# Thermostat_Schematic.net
KiCad netlist of a schematic drawn in EAGLE
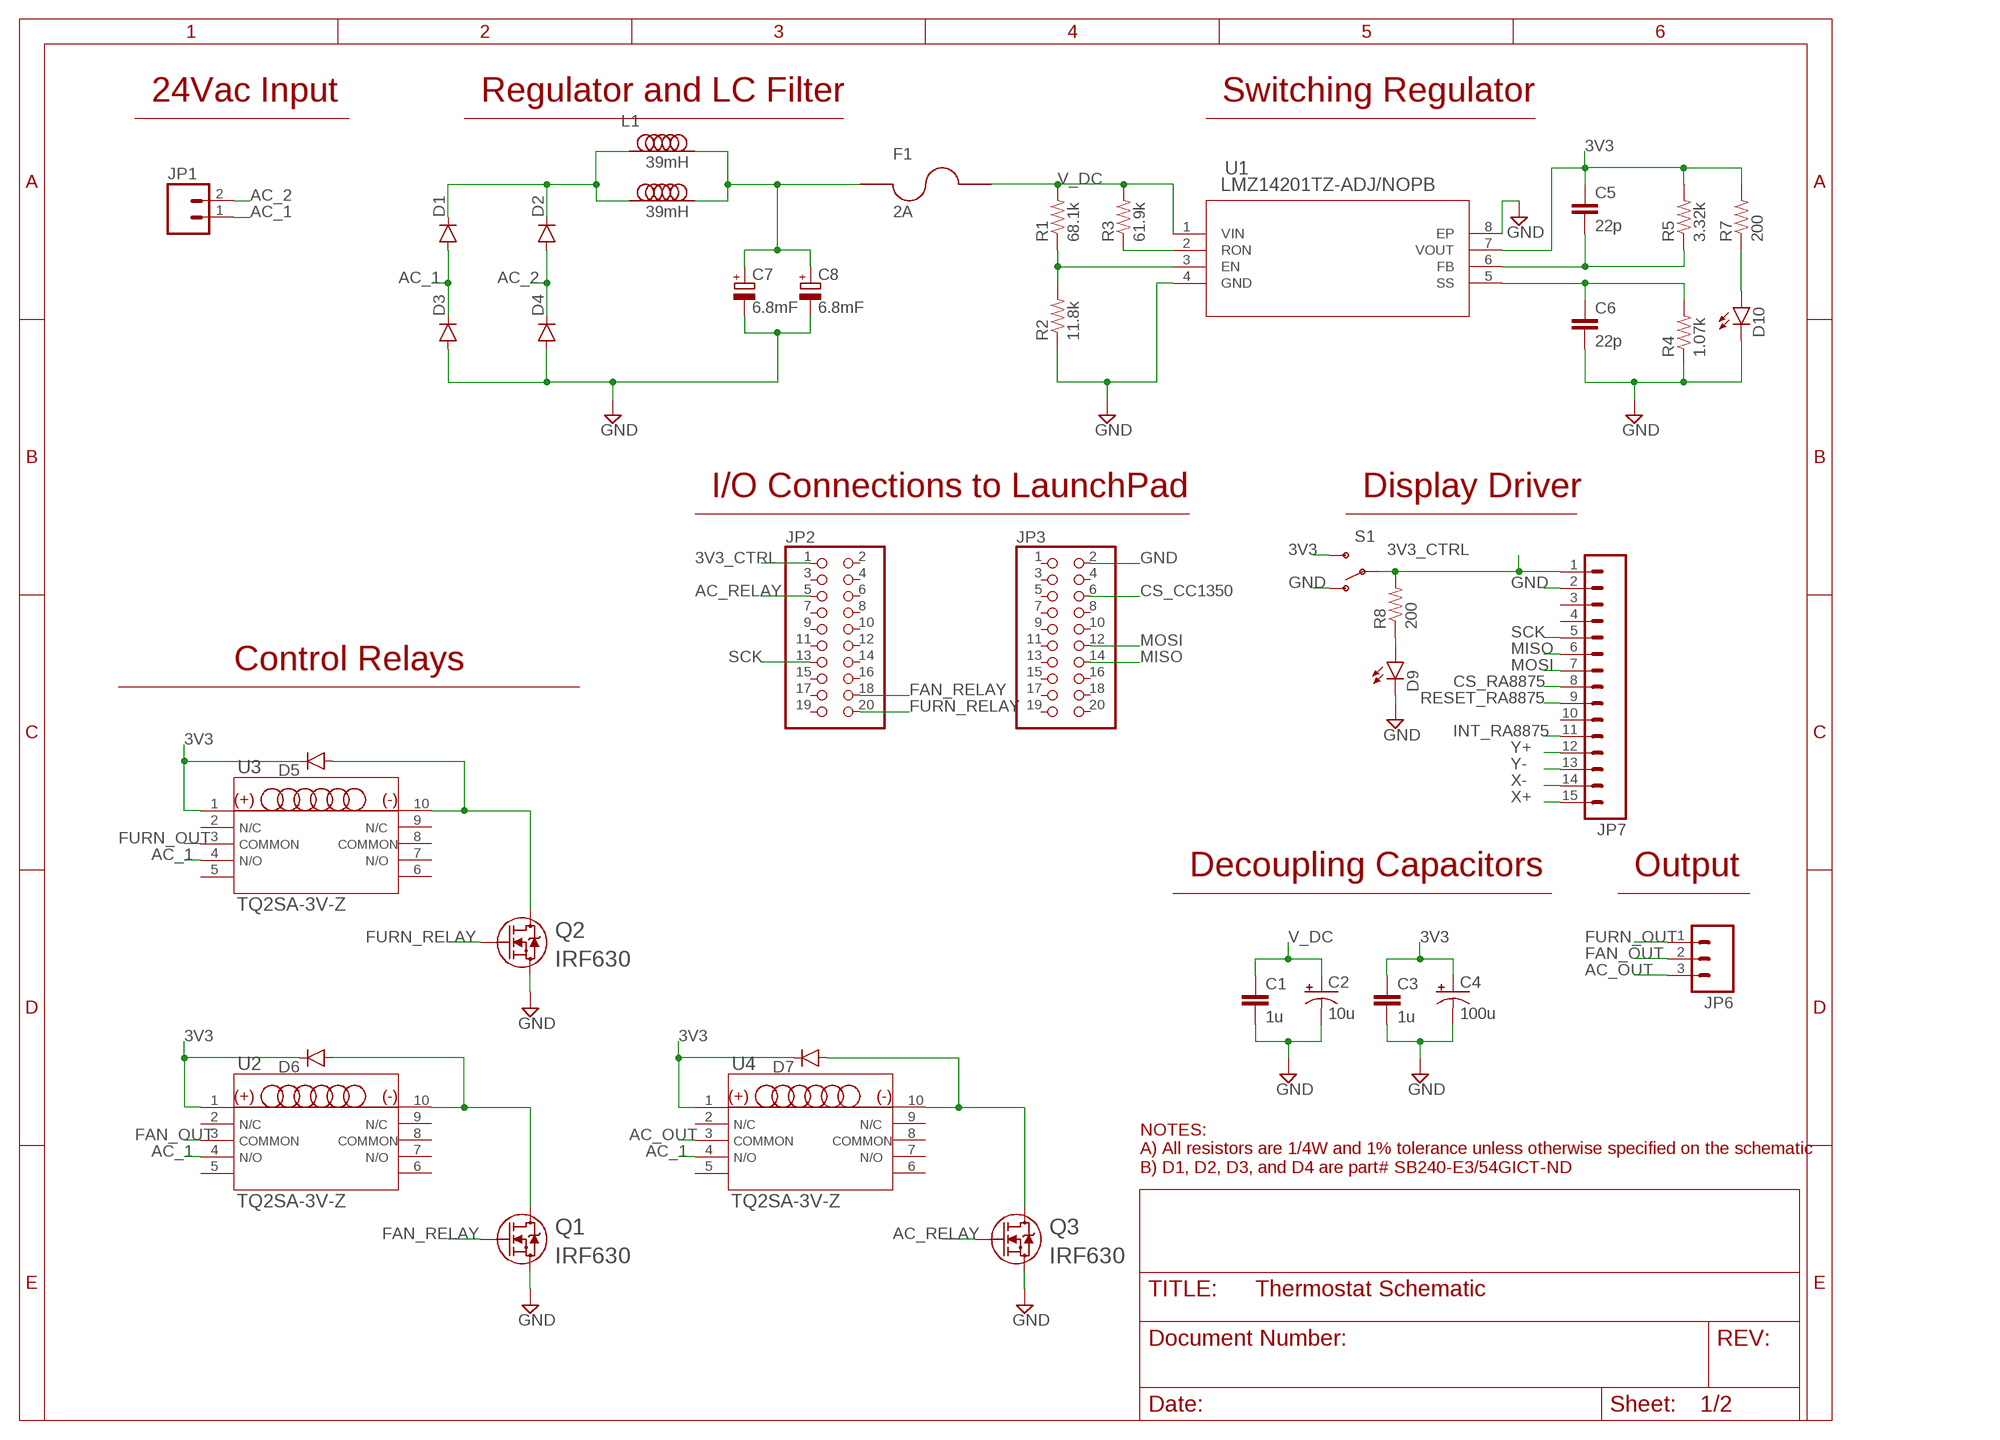
[diagram p0: schematic, sheet 1]
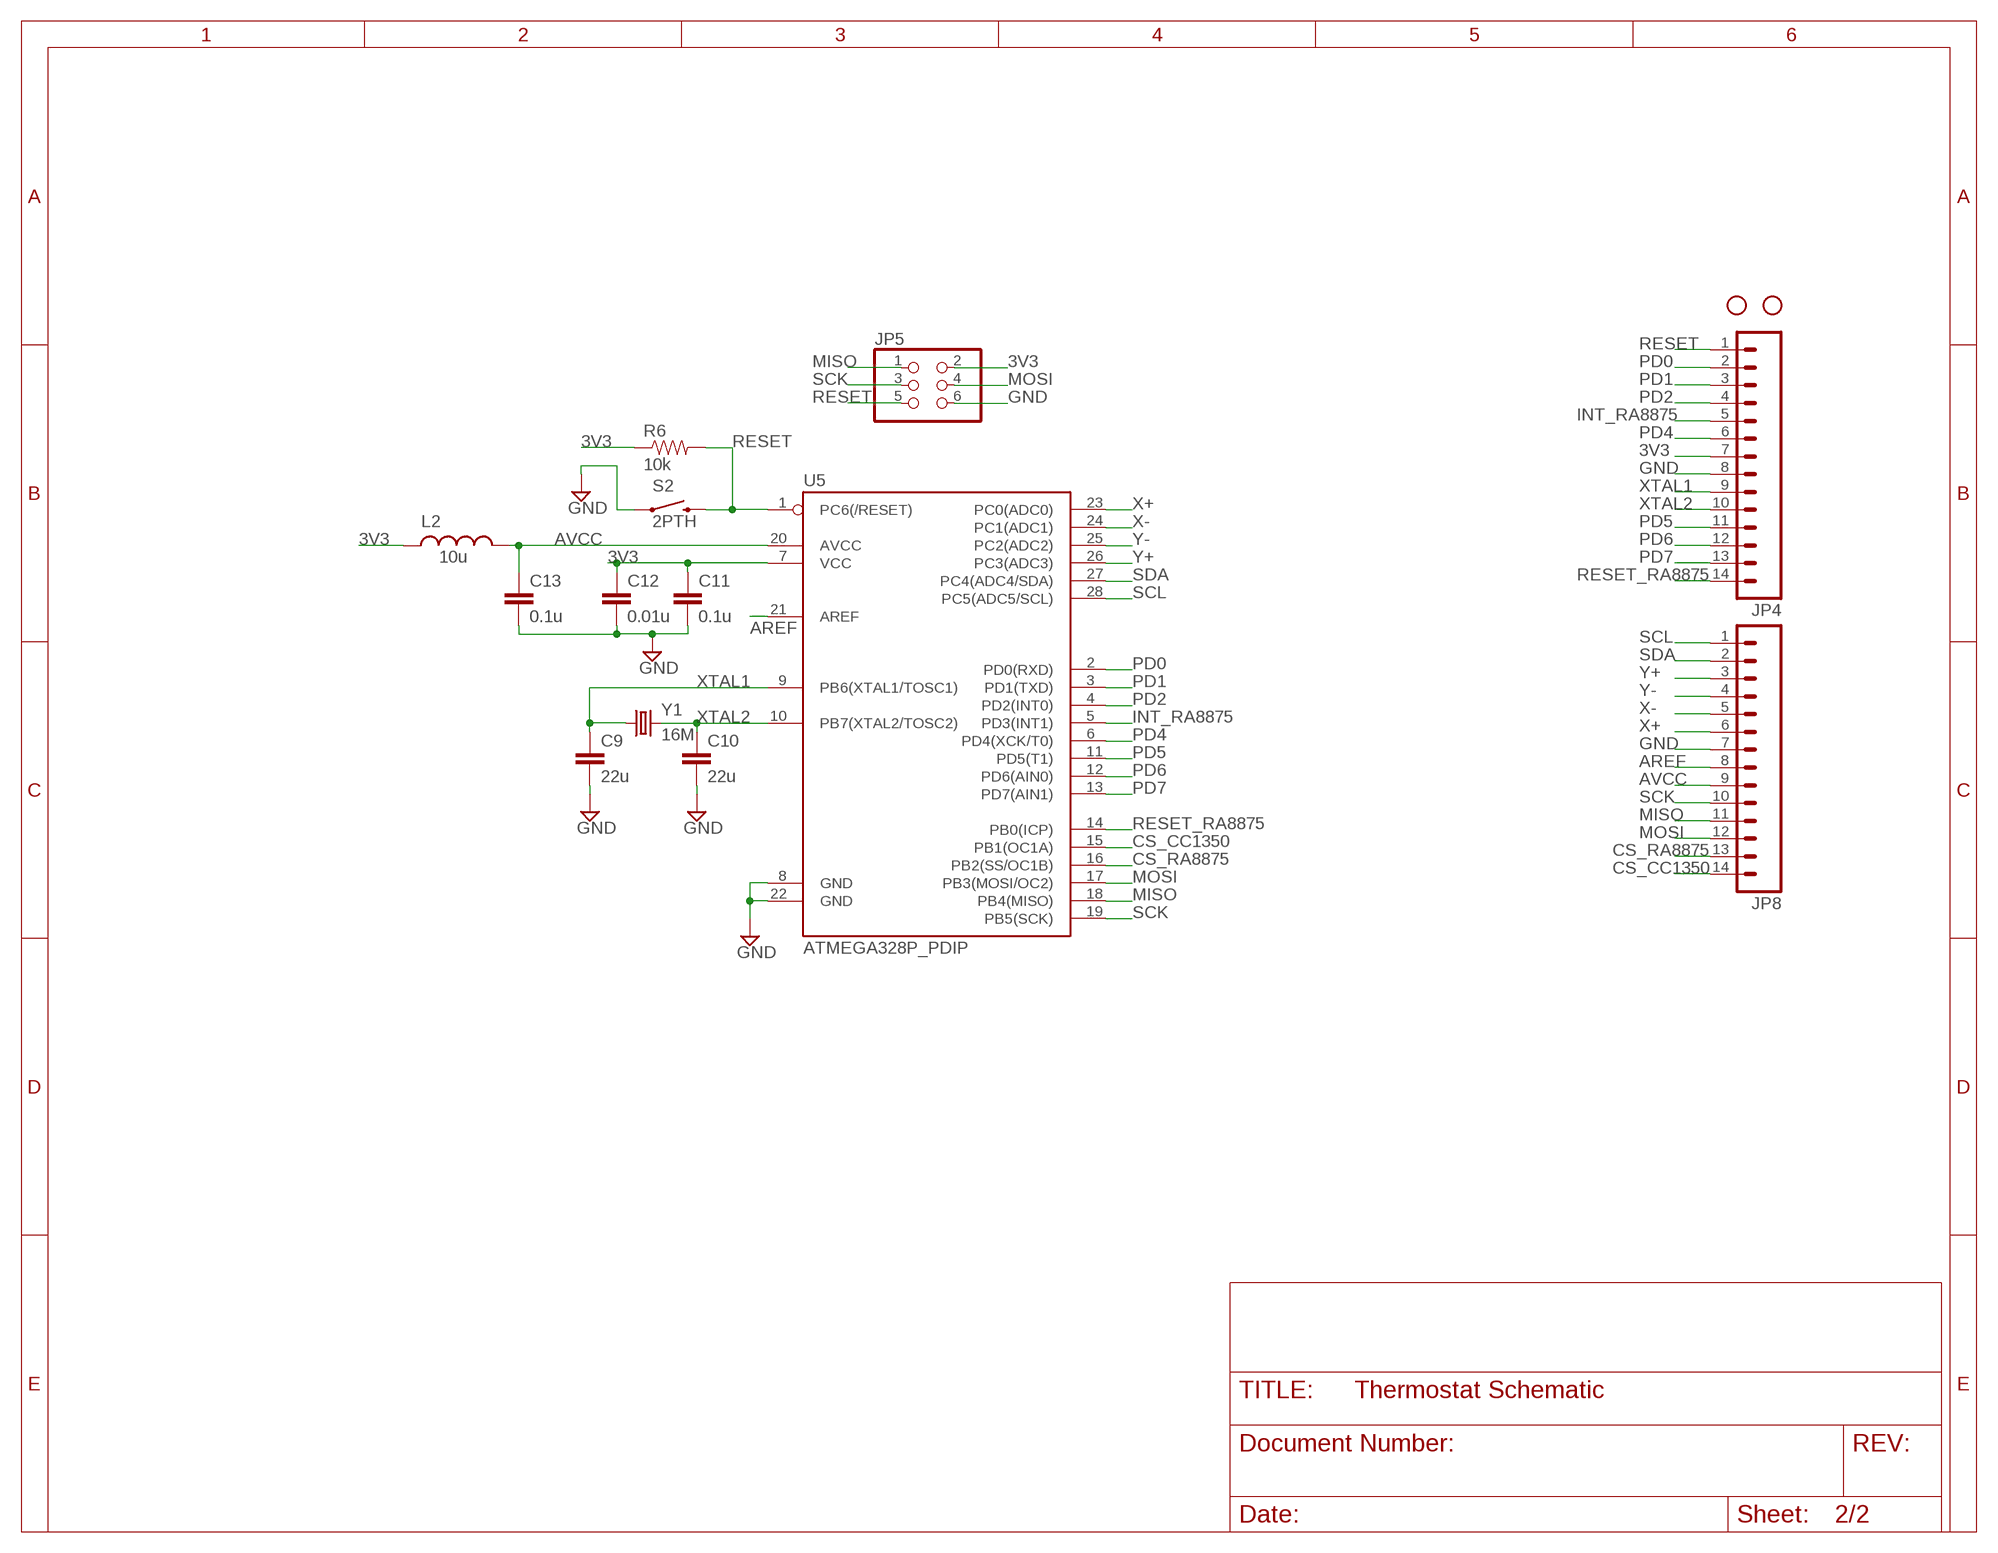
[diagram p1: schematic, sheet 2]

(export (version "E")
  (design (tool "Eeschema 10.0.6"))
  (components
    (comp (ref "C1")
      (value "1u")
      (footprint "eagle-import:CAP-PTH-5MM")
      (libsource (lib "eagle-import") (part "CAPPTH1"))
    )
    (comp (ref "C2")
      (value "10u")
      (footprint "eagle-import:CPOL-RADIAL-10UF-25V")
      (libsource (lib "eagle-import") (part "CAP_POLPTH2"))
    )
    (comp (ref "C3")
      (value "1u")
      (footprint "eagle-import:CAP-PTH-5MM")
      (libsource (lib "eagle-import") (part "CAPPTH1"))
    )
    (comp (ref "C4")
      (value "100u")
      (footprint "eagle-import:CPOL-RADIAL-1000UF-25V")
      (libsource (lib "eagle-import") (part "CAP_POLPTH4"))
    )
    (comp (ref "C5")
      (value "22p")
      (footprint "eagle-import:CAP-PTH-5MM")
      (libsource (lib "eagle-import") (part "CAPPTH1"))
    )
    (comp (ref "C6")
      (value "22p")
      (footprint "eagle-import:CAP-PTH-5MM")
      (libsource (lib "eagle-import") (part "CAPPTH1"))
    )
    (comp (ref "C7")
      (value "6.8mF")
      (footprint "eagle-import:E7,5-16")
      (libsource (lib "eagle-import") (part "CPOL-EUE7.5-16"))
    )
    (comp (ref "C8")
      (value "6.8mF")
      (footprint "eagle-import:E7,5-16")
      (libsource (lib "eagle-import") (part "CPOL-EUE7.5-16"))
    )
    (comp (ref "D1")
      (value "DIODEPTH")
      (footprint "eagle-import:DIODE-1N4001")
      (libsource (lib "eagle-import") (part "DIODEPTH"))
    )
    (comp (ref "D2")
      (value "DIODEPTH")
      (footprint "eagle-import:DIODE-1N4001")
      (libsource (lib "eagle-import") (part "DIODEPTH"))
    )
    (comp (ref "D3")
      (value "DIODEPTH")
      (footprint "eagle-import:DIODE-1N4001")
      (libsource (lib "eagle-import") (part "DIODEPTH"))
    )
    (comp (ref "D4")
      (value "DIODEPTH")
      (footprint "eagle-import:DIODE-1N4001")
      (libsource (lib "eagle-import") (part "DIODEPTH"))
    )
    (comp (ref "D5")
      (value "DIODEPTH")
      (footprint "eagle-import:DIODE-1N4001")
      (libsource (lib "eagle-import") (part "DIODEPTH"))
    )
    (comp (ref "D6")
      (value "DIODEPTH")
      (footprint "eagle-import:DIODE-1N4001")
      (libsource (lib "eagle-import") (part "DIODEPTH"))
    )
    (comp (ref "D7")
      (value "DIODEPTH")
      (footprint "eagle-import:DIODE-1N4001")
      (libsource (lib "eagle-import") (part "DIODEPTH"))
    )
    (comp (ref "D9")
      (value "LED1206")
      (footprint "eagle-import:LED-1206")
      (libsource (lib "eagle-import") (part "LED1206"))
    )
    (comp (ref "D10")
      (value "LED1206")
      (footprint "eagle-import:LED-1206")
      (libsource (lib "eagle-import") (part "LED1206"))
    )
    (comp (ref "F1")
      (value "2A")
      (footprint "eagle-import:36-3550-2-ND")
      (libsource (lib "eagle-import") (part "FUSEHOLDER_36-3550-2-ND"))
    )
    (comp (ref "JP1")
      (value "M023.5MM")
      (footprint "eagle-import:SCREWTERMINAL-3.5MM-2")
      (libsource (lib "eagle-import") (part "M023.5MM"))
    )
    (comp (ref "JP2")
      (value "PINHD-2X10")
      (footprint "eagle-import:2X10")
      (libsource (lib "eagle-import") (part "PINHD-2X10"))
    )
    (comp (ref "JP3")
      (value "PINHD-2X10")
      (footprint "eagle-import:2X10")
      (libsource (lib "eagle-import") (part "PINHD-2X10"))
    )
    (comp (ref "JP6")
      (value "M03SCREW")
      (footprint "eagle-import:SCREWTERMINAL-3.5MM-3")
      (libsource (lib "eagle-import") (part "M03SCREW"))
    )
    (comp (ref "JP7")
      (value "M15")
      (footprint "eagle-import:1X15")
      (libsource (lib "eagle-import") (part "M15"))
    )
    (comp (ref "L1")
      (value "39mH")
      (footprint "eagle-import:B82733F")
      (libsource (lib "eagle-import") (part "B82733F"))
    )
    (comp (ref "Q1")
      (value "IRF630")
      (footprint "eagle-import:TO-220")
      (libsource (lib "eagle-import") (part "IRF630"))
    )
    (comp (ref "Q2")
      (value "IRF630")
      (footprint "eagle-import:TO-220")
      (libsource (lib "eagle-import") (part "IRF630"))
    )
    (comp (ref "Q3")
      (value "IRF630")
      (footprint "eagle-import:TO-220")
      (libsource (lib "eagle-import") (part "IRF630"))
    )
    (comp (ref "R1")
      (value "68.1k")
      (footprint "eagle-import:AXIAL-0.3")
      (libsource (lib "eagle-import") (part "SparkFun-Resistors_RESISTORAXIAL-0.3"))
    )
    (comp (ref "R2")
      (value "11.8k")
      (footprint "eagle-import:AXIAL-0.3")
      (libsource (lib "eagle-import") (part "SparkFun-Resistors_RESISTORAXIAL-0.3"))
    )
    (comp (ref "R3")
      (value "61.9k")
      (footprint "eagle-import:AXIAL-0.3")
      (libsource (lib "eagle-import") (part "SparkFun-Resistors_RESISTORAXIAL-0.3"))
    )
    (comp (ref "R4")
      (value "1.07k")
      (footprint "eagle-import:AXIAL-0.3")
      (libsource (lib "eagle-import") (part "SparkFun-Resistors_RESISTORAXIAL-0.3"))
    )
    (comp (ref "R5")
      (value "3.32k")
      (footprint "eagle-import:AXIAL-0.3")
      (libsource (lib "eagle-import") (part "SparkFun-Resistors_RESISTORAXIAL-0.3"))
    )
    (comp (ref "R7")
      (value "200")
      (footprint "eagle-import:AXIAL-0.3")
      (libsource (lib "eagle-import") (part "SparkFun-Resistors_RESISTORAXIAL-0.3"))
    )
    (comp (ref "R8")
      (value "200")
      (footprint "eagle-import:AXIAL-0.3")
      (libsource (lib "eagle-import") (part "SparkFun-Resistors_RESISTORAXIAL-0.3"))
    )
    (comp (ref "S1")
      (value "SWITCH-SPDTPTH")
      (footprint "eagle-import:SWITCH-SPDT")
      (libsource (lib "eagle-import") (part "SWITCH-SPDTPTH"))
    )
    (comp (ref "U1")
      (value "LMZ14201TZ-ADJ/NOPB")
      (footprint "eagle-import:TZA07A")
      (fields (field (name "MANUFACTURER_PART_NUMBER") "LMZ14201TZADJNOPB"))
      (libsource (lib "eagle-import") (part "LMZ14201TZ-ADJ/NOPB"))
    )
    (comp (ref "U2")
      (value "TQ2SA-3V-Z")
      (footprint "eagle-import:RELAY_TQ2_SA-M")
      (fields (field (name "MANUFACTURER_PART_NUMBER") "TQ2SA3VZ"))
      (libsource (lib "eagle-import") (part "TQ2SA-3V-ZRELAY_TQ2_SA-M"))
    )
    (comp (ref "U3")
      (value "TQ2SA-3V-Z")
      (footprint "eagle-import:RELAY_TQ2_SA-M")
      (fields (field (name "MANUFACTURER_PART_NUMBER") "TQ2SA3VZ"))
      (libsource (lib "eagle-import") (part "TQ2SA-3V-ZRELAY_TQ2_SA-M"))
    )
    (comp (ref "U4")
      (value "TQ2SA-3V-Z")
      (footprint "eagle-import:RELAY_TQ2_SA-M")
      (fields (field (name "MANUFACTURER_PART_NUMBER") "TQ2SA3VZ"))
      (libsource (lib "eagle-import") (part "TQ2SA-3V-ZRELAY_TQ2_SA-M"))
    )
    (comp (ref "C9")
      (value "22u")
      (footprint "eagle-import:CAP-PTH-5MM")
      (libsource (lib "eagle-import") (part "CAPPTH1"))
    )
    (comp (ref "C10")
      (value "22u")
      (footprint "eagle-import:CAP-PTH-5MM")
      (libsource (lib "eagle-import") (part "CAPPTH1"))
    )
    (comp (ref "C11")
      (value "0.1u")
      (footprint "eagle-import:CAP-PTH-5MM")
      (libsource (lib "eagle-import") (part "CAPPTH1"))
    )
    (comp (ref "C12")
      (value "0.01u")
      (footprint "eagle-import:CAP-PTH-5MM")
      (libsource (lib "eagle-import") (part "CAPPTH1"))
    )
    (comp (ref "C13")
      (value "0.1u")
      (footprint "eagle-import:CAP-PTH-5MM")
      (libsource (lib "eagle-import") (part "CAPPTH1"))
    )
    (comp (ref "JP4")
      (value "M14")
      (footprint "eagle-import:1X14")
      (libsource (lib "eagle-import") (part "M14"))
    )
    (comp (ref "JP5")
      (value "PINHD-2X3")
      (footprint "eagle-import:2X03")
      (libsource (lib "eagle-import") (part "PINHD-2X3"))
    )
    (comp (ref "JP8")
      (value "M14")
      (footprint "eagle-import:1X14")
      (libsource (lib "eagle-import") (part "M14"))
    )
    (comp (ref "L2")
      (value "10u")
      (footprint "eagle-import:AXIAL-0.6")
      (libsource (lib "eagle-import") (part "INDUCTORAXIAL-0.6"))
    )
    (comp (ref "R6")
      (value "10k")
      (footprint "eagle-import:AXIAL-0.3")
      (libsource (lib "eagle-import") (part "RESISTORAXIAL-0.3"))
    )
    (comp (ref "S2")
      (value "2PTH")
      (footprint "eagle-import:TACTILE-PTH-EZ")
      (libsource (lib "eagle-import") (part "SWITCH-MOMENTARY-2PTH_EZ"))
    )
    (comp (ref "STANDOFF3")
      (value "STAND-OFFTIGHT")
      (footprint "eagle-import:STAND-OFF-TIGHT")
      (libsource (lib "eagle-import") (part "STAND-OFFTIGHT"))
    )
    (comp (ref "STANDOFF4")
      (value "STAND-OFFTIGHT")
      (footprint "eagle-import:STAND-OFF-TIGHT")
      (libsource (lib "eagle-import") (part "STAND-OFFTIGHT"))
    )
    (comp (ref "U5")
      (value "ATMEGA328P_PDIP")
      (footprint "eagle-import:DIL28-3")
      (libsource (lib "eagle-import") (part "ATMEGA328P_PDIP"))
    )
    (comp (ref "Y1")
      (value "16M")
      (footprint "eagle-import:HC49US")
      (libsource (lib "eagle-import") (part "CRYSTALHC49US"))
    )
  )
  (nets
    (net (code "1") (name "3V3") (class "Default")
      (node (ref "C11") (pin "1") (pinfunction "1_1") (pintype "passive"))
      (node (ref "C12") (pin "1") (pinfunction "1_1") (pintype "passive"))
      (node (ref "C3") (pin "1") (pinfunction "1_1") (pintype "passive"))
      (node (ref "C4") (pin "+") (pinfunction "+_+") (pintype "passive"))
      (node (ref "C5") (pin "1") (pinfunction "1_1") (pintype "passive"))
      (node (ref "D5") (pin "C") (pinfunction "C_C") (pintype "passive"))
      (node (ref "D6") (pin "C") (pinfunction "C_C") (pintype "passive"))
      (node (ref "D7") (pin "C") (pinfunction "C_C") (pintype "passive"))
      (node (ref "JP4") (pin "7") (pinfunction "7_7") (pintype "passive"))
      (node (ref "JP5") (pin "2") (pinfunction "2_2") (pintype "passive"))
      (node (ref "L2") (pin "P$1") (pinfunction "1_P$1") (pintype "passive"))
      (node (ref "R5") (pin "P$2") (pinfunction "2_P$2") (pintype "passive"))
      (node (ref "R6") (pin "P$1") (pinfunction "1_P$1") (pintype "passive"))
      (node (ref "R7") (pin "P$2") (pinfunction "2_P$2") (pintype "passive"))
      (node (ref "S1") (pin "3") (pinfunction "S_3") (pintype "passive"))
      (node (ref "U1") (pin "7") (pinfunction "VOUT_7") (pintype "output"))
      (node (ref "U2") (pin "1") (pinfunction "1_1") (pintype "passive"))
      (node (ref "U3") (pin "1") (pinfunction "1_1") (pintype "passive"))
      (node (ref "U4") (pin "1") (pinfunction "1_1") (pintype "passive"))
      (node (ref "U5") (pin "7") (pinfunction "VCC_7") (pintype "bidirectional"))
    )
    (net (code "2") (name "3V3_CTRL") (class "Default")
      (node (ref "JP2") (pin "1") (pinfunction "1_1") (pintype "passive"))
      (node (ref "JP7") (pin "1") (pinfunction "1_1") (pintype "passive"))
      (node (ref "R8") (pin "P$2") (pinfunction "2_P$2") (pintype "passive"))
      (node (ref "S1") (pin "2") (pinfunction "P_2") (pintype "passive"))
    )
    (net (code "3") (name "AC_1") (class "Default")
      (node (ref "D1") (pin "A") (pinfunction "A_A") (pintype "passive"))
      (node (ref "D3") (pin "C") (pinfunction "C_C") (pintype "passive"))
      (node (ref "JP1") (pin "1") (pinfunction "1_1") (pintype "passive"))
      (node (ref "U2") (pin "4") (pinfunction "4_4") (pintype "passive"))
      (node (ref "U3") (pin "4") (pinfunction "4_4") (pintype "passive"))
      (node (ref "U4") (pin "4") (pinfunction "4_4") (pintype "passive"))
    )
    (net (code "4") (name "AC_2") (class "Default")
      (node (ref "D2") (pin "A") (pinfunction "A_A") (pintype "passive"))
      (node (ref "D4") (pin "C") (pinfunction "C_C") (pintype "passive"))
      (node (ref "JP1") (pin "2") (pinfunction "2_2") (pintype "passive"))
    )
    (net (code "5") (name "AC_OUT") (class "Default")
      (node (ref "JP6") (pin "3") (pinfunction "3_3") (pintype "passive"))
      (node (ref "U4") (pin "3") (pinfunction "3_3") (pintype "passive"))
    )
    (net (code "6") (name "AC_RELAY") (class "Default")
      (node (ref "JP2") (pin "5") (pinfunction "5_5") (pintype "passive"))
      (node (ref "Q3") (pin "1") (pinfunction "1_1") (pintype "passive"))
    )
    (net (code "7") (name "AREF") (class "Default")
      (node (ref "JP8") (pin "8") (pinfunction "8_8") (pintype "passive"))
      (node (ref "U5") (pin "21") (pinfunction "AREF_21") (pintype "bidirectional"))
    )
    (net (code "8") (name "AVCC") (class "Default")
      (node (ref "C13") (pin "1") (pinfunction "1_1") (pintype "passive"))
      (node (ref "JP8") (pin "9") (pinfunction "9_9") (pintype "passive"))
      (node (ref "L2") (pin "P$2") (pinfunction "2_P$2") (pintype "passive"))
      (node (ref "U5") (pin "20") (pinfunction "AVCC_20") (pintype "bidirectional"))
    )
    (net (code "9") (name "CS_CC1350") (class "Default")
      (node (ref "JP3") (pin "6") (pinfunction "6_6") (pintype "passive"))
      (node (ref "JP8") (pin "14") (pinfunction "14_14") (pintype "passive"))
      (node (ref "U5") (pin "15") (pinfunction "PB1(OC1A)_15") (pintype "bidirectional"))
    )
    (net (code "10") (name "CS_RA8875") (class "Default")
      (node (ref "JP7") (pin "8") (pinfunction "8_8") (pintype "passive"))
      (node (ref "JP8") (pin "13") (pinfunction "13_13") (pintype "passive"))
      (node (ref "U5") (pin "16") (pinfunction "PB2(SS/OC1B)_16") (pintype "bidirectional"))
    )
    (net (code "11") (name "FAN_OUT") (class "Default")
      (node (ref "JP6") (pin "2") (pinfunction "2_2") (pintype "passive"))
      (node (ref "U2") (pin "3") (pinfunction "3_3") (pintype "passive"))
    )
    (net (code "12") (name "FAN_RELAY") (class "Default")
      (node (ref "JP2") (pin "18") (pinfunction "18_18") (pintype "passive"))
      (node (ref "Q1") (pin "1") (pinfunction "1_1") (pintype "passive"))
    )
    (net (code "13") (name "FURN_OUT") (class "Default")
      (node (ref "JP6") (pin "1") (pinfunction "1_1") (pintype "passive"))
      (node (ref "U3") (pin "3") (pinfunction "3_3") (pintype "passive"))
    )
    (net (code "14") (name "FURN_RELAY") (class "Default")
      (node (ref "JP2") (pin "20") (pinfunction "20_20") (pintype "passive"))
      (node (ref "Q2") (pin "1") (pinfunction "1_1") (pintype "passive"))
    )
    (net (code "15") (name "GND") (class "Default")
      (node (ref "C1") (pin "2") (pinfunction "2_2") (pintype "passive"))
      (node (ref "C10") (pin "2") (pinfunction "2_2") (pintype "passive"))
      (node (ref "C11") (pin "2") (pinfunction "2_2") (pintype "passive"))
      (node (ref "C12") (pin "2") (pinfunction "2_2") (pintype "passive"))
      (node (ref "C13") (pin "2") (pinfunction "2_2") (pintype "passive"))
      (node (ref "C2") (pin "2") (pinfunction "-_2") (pintype "passive"))
      (node (ref "C3") (pin "2") (pinfunction "2_2") (pintype "passive"))
      (node (ref "C4") (pin "-") (pinfunction "-_-") (pintype "passive"))
      (node (ref "C6") (pin "2") (pinfunction "2_2") (pintype "passive"))
      (node (ref "C7") (pin "-") (pinfunction "-_-") (pintype "passive"))
      (node (ref "C8") (pin "-") (pinfunction "-_-") (pintype "passive"))
      (node (ref "C9") (pin "2") (pinfunction "2_2") (pintype "passive"))
      (node (ref "D10") (pin "C") (pinfunction "C_C") (pintype "passive"))
      (node (ref "D3") (pin "A") (pinfunction "A_A") (pintype "passive"))
      (node (ref "D4") (pin "A") (pinfunction "A_A") (pintype "passive"))
      (node (ref "D9") (pin "C") (pinfunction "C_C") (pintype "passive"))
      (node (ref "JP3") (pin "2") (pinfunction "2_2") (pintype "passive"))
      (node (ref "JP4") (pin "8") (pinfunction "8_8") (pintype "passive"))
      (node (ref "JP5") (pin "6") (pinfunction "6_6") (pintype "passive"))
      (node (ref "JP7") (pin "2") (pinfunction "2_2") (pintype "passive"))
      (node (ref "JP8") (pin "7") (pinfunction "7_7") (pintype "passive"))
      (node (ref "Q1") (pin "3") (pinfunction "3_3") (pintype "passive"))
      (node (ref "Q2") (pin "3") (pinfunction "3_3") (pintype "passive"))
      (node (ref "Q3") (pin "3") (pinfunction "3_3") (pintype "passive"))
      (node (ref "R2") (pin "P$1") (pinfunction "1_P$1") (pintype "passive"))
      (node (ref "R4") (pin "P$1") (pinfunction "1_P$1") (pintype "passive"))
      (node (ref "S1") (pin "1") (pinfunction "O_1") (pintype "passive"))
      (node (ref "S2") (pin "1") (pinfunction "1_1") (pintype "passive"))
      (node (ref "U1") (pin "4") (pinfunction "GND_4") (pintype "power_in"))
      (node (ref "U1") (pin "8") (pinfunction "EP_8") (pintype "passive"))
      (node (ref "U5") (pin "22") (pinfunction "GND_22") (pintype "bidirectional"))
      (node (ref "U5") (pin "8") (pinfunction "GND_8") (pintype "bidirectional"))
    )
    (net (code "16") (name "INT_RA8875") (class "Default")
      (node (ref "JP4") (pin "5") (pinfunction "5_5") (pintype "passive"))
      (node (ref "JP7") (pin "11") (pinfunction "11_11") (pintype "passive"))
      (node (ref "U5") (pin "5") (pinfunction "PD3(INT1)_5") (pintype "bidirectional"))
    )
    (net (code "17") (name "MISO") (class "Default")
      (node (ref "JP3") (pin "14") (pinfunction "14_14") (pintype "passive"))
      (node (ref "JP5") (pin "1") (pinfunction "1_1") (pintype "passive"))
      (node (ref "JP7") (pin "6") (pinfunction "6_6") (pintype "passive"))
      (node (ref "JP8") (pin "11") (pinfunction "11_11") (pintype "passive"))
      (node (ref "U5") (pin "18") (pinfunction "PB4(MISO)_18") (pintype "bidirectional"))
    )
    (net (code "18") (name "MOSI") (class "Default")
      (node (ref "JP3") (pin "12") (pinfunction "12_12") (pintype "passive"))
      (node (ref "JP5") (pin "4") (pinfunction "4_4") (pintype "passive"))
      (node (ref "JP7") (pin "7") (pinfunction "7_7") (pintype "passive"))
      (node (ref "JP8") (pin "12") (pinfunction "12_12") (pintype "passive"))
      (node (ref "U5") (pin "17") (pinfunction "PB3(MOSI/OC2)_17") (pintype "bidirectional"))
    )
    (net (code "19") (name "Net-(C7-Pad+)") (class "Default")
      (node (ref "C7") (pin "+") (pinfunction "+_+") (pintype "passive"))
      (node (ref "C8") (pin "+") (pinfunction "+_+") (pintype "passive"))
      (node (ref "F1") (pin "PIN1A") (pinfunction "PIN1_PIN1A") (pintype "bidirectional"))
      (node (ref "F1") (pin "PIN1B") (pinfunction "PIN1_PIN1B") (pintype "bidirectional"))
      (node (ref "L1") (pin "P$2") (pinfunction "P$2_P$2") (pintype "bidirectional"))
      (node (ref "L1") (pin "P$3") (pinfunction "P$3_P$3") (pintype "bidirectional"))
    )
    (net (code "20") (name "Net-(D1-PadC)") (class "Default")
      (node (ref "D1") (pin "C") (pinfunction "C_C") (pintype "passive"))
      (node (ref "D2") (pin "C") (pinfunction "C_C") (pintype "passive"))
      (node (ref "L1") (pin "P$1") (pinfunction "P$1_P$1") (pintype "bidirectional"))
      (node (ref "L1") (pin "P$4") (pinfunction "P$4_P$4") (pintype "bidirectional"))
    )
    (net (code "21") (name "Net-(D5-PadA)") (class "Default")
      (node (ref "D5") (pin "A") (pinfunction "A_A") (pintype "passive"))
      (node (ref "Q2") (pin "2") (pinfunction "2_2") (pintype "passive"))
      (node (ref "U3") (pin "10") (pinfunction "10_10") (pintype "passive"))
    )
    (net (code "22") (name "Net-(D6-PadA)") (class "Default")
      (node (ref "D6") (pin "A") (pinfunction "A_A") (pintype "passive"))
      (node (ref "Q1") (pin "2") (pinfunction "2_2") (pintype "passive"))
      (node (ref "U2") (pin "10") (pinfunction "10_10") (pintype "passive"))
    )
    (net (code "23") (name "Net-(D7-PadA)") (class "Default")
      (node (ref "D7") (pin "A") (pinfunction "A_A") (pintype "passive"))
      (node (ref "Q3") (pin "2") (pinfunction "2_2") (pintype "passive"))
      (node (ref "U4") (pin "10") (pinfunction "10_10") (pintype "passive"))
    )
    (net (code "24") (name "Net-(R1-1)") (class "Default")
      (node (ref "R1") (pin "P$1") (pinfunction "1_P$1") (pintype "passive"))
      (node (ref "R2") (pin "P$2") (pinfunction "2_P$2") (pintype "passive"))
      (node (ref "U1") (pin "3") (pinfunction "EN_3") (pintype "input"))
    )
    (net (code "25") (name "Net-(R3-1)") (class "Default")
      (node (ref "R3") (pin "P$1") (pinfunction "1_P$1") (pintype "passive"))
      (node (ref "U1") (pin "2") (pinfunction "RON_2") (pintype "passive"))
    )
    (net (code "26") (name "Net-(R4-2)") (class "Default")
      (node (ref "C6") (pin "1") (pinfunction "1_1") (pintype "passive"))
      (node (ref "R4") (pin "P$2") (pinfunction "2_P$2") (pintype "passive"))
      (node (ref "U1") (pin "5") (pinfunction "SS_5") (pintype "passive"))
    )
    (net (code "27") (name "Net-(R5-1)") (class "Default")
      (node (ref "C5") (pin "2") (pinfunction "2_2") (pintype "passive"))
      (node (ref "R5") (pin "P$1") (pinfunction "1_P$1") (pintype "passive"))
      (node (ref "U1") (pin "6") (pinfunction "FB_6") (pintype "input"))
    )
    (net (code "28") (name "Net-(R7-1)") (class "Default")
      (node (ref "D10") (pin "A") (pinfunction "A_A") (pintype "passive"))
      (node (ref "R7") (pin "P$1") (pinfunction "1_P$1") (pintype "passive"))
    )
    (net (code "29") (name "Net-(R8-1)") (class "Default")
      (node (ref "D9") (pin "A") (pinfunction "A_A") (pintype "passive"))
      (node (ref "R8") (pin "P$1") (pinfunction "1_P$1") (pintype "passive"))
    )
    (net (code "30") (name "PD0") (class "Default")
      (node (ref "JP4") (pin "2") (pinfunction "2_2") (pintype "passive"))
      (node (ref "U5") (pin "2") (pinfunction "PD0(RXD)_2") (pintype "bidirectional"))
    )
    (net (code "31") (name "PD1") (class "Default")
      (node (ref "JP4") (pin "3") (pinfunction "3_3") (pintype "passive"))
      (node (ref "U5") (pin "3") (pinfunction "PD1(TXD)_3") (pintype "bidirectional"))
    )
    (net (code "32") (name "PD2") (class "Default")
      (node (ref "JP4") (pin "4") (pinfunction "4_4") (pintype "passive"))
      (node (ref "U5") (pin "4") (pinfunction "PD2(INT0)_4") (pintype "bidirectional"))
    )
    (net (code "33") (name "PD4") (class "Default")
      (node (ref "JP4") (pin "6") (pinfunction "6_6") (pintype "passive"))
      (node (ref "U5") (pin "6") (pinfunction "PD4(XCK/T0)_6") (pintype "bidirectional"))
    )
    (net (code "34") (name "PD5") (class "Default")
      (node (ref "JP4") (pin "11") (pinfunction "11_11") (pintype "passive"))
      (node (ref "U5") (pin "11") (pinfunction "PD5(T1)_11") (pintype "bidirectional"))
    )
    (net (code "35") (name "PD6") (class "Default")
      (node (ref "JP4") (pin "12") (pinfunction "12_12") (pintype "passive"))
      (node (ref "U5") (pin "12") (pinfunction "PD6(AIN0)_12") (pintype "bidirectional"))
    )
    (net (code "36") (name "PD7") (class "Default")
      (node (ref "JP4") (pin "13") (pinfunction "13_13") (pintype "passive"))
      (node (ref "U5") (pin "13") (pinfunction "PD7(AIN1)_13") (pintype "bidirectional"))
    )
    (net (code "37") (name "RESET") (class "Default")
      (node (ref "JP4") (pin "1") (pinfunction "1_1") (pintype "passive"))
      (node (ref "JP5") (pin "5") (pinfunction "5_5") (pintype "passive"))
      (node (ref "R6") (pin "P$2") (pinfunction "2_P$2") (pintype "passive"))
      (node (ref "S2") (pin "3") (pinfunction "2_3") (pintype "passive"))
      (node (ref "U5") (pin "1") (pinfunction "PC6(/RESET)_1") (pintype "bidirectional"))
    )
    (net (code "38") (name "RESET_RA8875") (class "Default")
      (node (ref "JP4") (pin "14") (pinfunction "14_14") (pintype "passive"))
      (node (ref "JP7") (pin "9") (pinfunction "9_9") (pintype "passive"))
      (node (ref "U5") (pin "14") (pinfunction "PB0(ICP)_14") (pintype "bidirectional"))
    )
    (net (code "39") (name "SCK") (class "Default")
      (node (ref "JP2") (pin "13") (pinfunction "13_13") (pintype "passive"))
      (node (ref "JP5") (pin "3") (pinfunction "3_3") (pintype "passive"))
      (node (ref "JP7") (pin "5") (pinfunction "5_5") (pintype "passive"))
      (node (ref "JP8") (pin "10") (pinfunction "10_10") (pintype "passive"))
      (node (ref "U5") (pin "19") (pinfunction "PB5(SCK)_19") (pintype "bidirectional"))
    )
    (net (code "40") (name "SCL") (class "Default")
      (node (ref "JP8") (pin "1") (pinfunction "1_1") (pintype "passive"))
      (node (ref "U5") (pin "28") (pinfunction "PC5(ADC5/SCL)_28") (pintype "bidirectional"))
    )
    (net (code "41") (name "SDA") (class "Default")
      (node (ref "JP8") (pin "2") (pinfunction "2_2") (pintype "passive"))
      (node (ref "U5") (pin "27") (pinfunction "PC4(ADC4/SDA)_27") (pintype "bidirectional"))
    )
    (net (code "42") (name "V_DC") (class "Default")
      (node (ref "C1") (pin "1") (pinfunction "1_1") (pintype "passive"))
      (node (ref "C2") (pin "1") (pinfunction "+_1") (pintype "passive"))
      (node (ref "F1") (pin "PIN2A") (pinfunction "PIN2_PIN2A") (pintype "bidirectional"))
      (node (ref "F1") (pin "PIN2B") (pinfunction "PIN2_PIN2B") (pintype "bidirectional"))
      (node (ref "R1") (pin "P$2") (pinfunction "2_P$2") (pintype "passive"))
      (node (ref "R3") (pin "P$2") (pinfunction "2_P$2") (pintype "passive"))
      (node (ref "U1") (pin "1") (pinfunction "VIN_1") (pintype "input"))
    )
    (net (code "43") (name "X+") (class "Default")
      (node (ref "JP7") (pin "15") (pinfunction "15_15") (pintype "passive"))
      (node (ref "JP8") (pin "6") (pinfunction "6_6") (pintype "passive"))
      (node (ref "U5") (pin "23") (pinfunction "PC0(ADC0)_23") (pintype "bidirectional"))
    )
    (net (code "44") (name "X-") (class "Default")
      (node (ref "JP7") (pin "14") (pinfunction "14_14") (pintype "passive"))
      (node (ref "JP8") (pin "5") (pinfunction "5_5") (pintype "passive"))
      (node (ref "U5") (pin "24") (pinfunction "PC1(ADC1)_24") (pintype "bidirectional"))
    )
    (net (code "45") (name "XTAL1") (class "Default")
      (node (ref "C9") (pin "1") (pinfunction "1_1") (pintype "passive"))
      (node (ref "JP4") (pin "9") (pinfunction "9_9") (pintype "passive"))
      (node (ref "U5") (pin "9") (pinfunction "PB6(XTAL1/TOSC1)_9") (pintype "bidirectional"))
      (node (ref "Y1") (pin "1") (pinfunction "1_1") (pintype "passive"))
    )
    (net (code "46") (name "XTAL2") (class "Default")
      (node (ref "C10") (pin "1") (pinfunction "1_1") (pintype "passive"))
      (node (ref "JP4") (pin "10") (pinfunction "10_10") (pintype "passive"))
      (node (ref "U5") (pin "10") (pinfunction "PB7(XTAL2/TOSC2)_10") (pintype "bidirectional"))
      (node (ref "Y1") (pin "2") (pinfunction "2_2") (pintype "passive"))
    )
    (net (code "47") (name "Y+") (class "Default")
      (node (ref "JP7") (pin "12") (pinfunction "12_12") (pintype "passive"))
      (node (ref "JP8") (pin "3") (pinfunction "3_3") (pintype "passive"))
      (node (ref "U5") (pin "26") (pinfunction "PC3(ADC3)_26") (pintype "bidirectional"))
    )
    (net (code "48") (name "Y-") (class "Default")
      (node (ref "JP7") (pin "13") (pinfunction "13_13") (pintype "passive"))
      (node (ref "JP8") (pin "4") (pinfunction "4_4") (pintype "passive"))
      (node (ref "U5") (pin "25") (pinfunction "PC2(ADC2)_25") (pintype "bidirectional"))
    )
    (net (code "49") (name "unconnected-(JP2-Pad2)") (class "Default")
      (node (ref "JP2") (pin "2") (pinfunction "2_2") (pintype "passive"))
    )
    (net (code "50") (name "unconnected-(JP2-Pad3)") (class "Default")
      (node (ref "JP2") (pin "3") (pinfunction "3_3") (pintype "passive"))
    )
    (net (code "51") (name "unconnected-(JP2-Pad4)") (class "Default")
      (node (ref "JP2") (pin "4") (pinfunction "4_4") (pintype "passive"))
    )
    (net (code "52") (name "unconnected-(JP2-Pad6)") (class "Default")
      (node (ref "JP2") (pin "6") (pinfunction "6_6") (pintype "passive"))
    )
    (net (code "53") (name "unconnected-(JP2-Pad7)") (class "Default")
      (node (ref "JP2") (pin "7") (pinfunction "7_7") (pintype "passive"))
    )
    (net (code "54") (name "unconnected-(JP2-Pad8)") (class "Default")
      (node (ref "JP2") (pin "8") (pinfunction "8_8") (pintype "passive"))
    )
    (net (code "55") (name "unconnected-(JP2-Pad9)") (class "Default")
      (node (ref "JP2") (pin "9") (pinfunction "9_9") (pintype "passive"))
    )
    (net (code "56") (name "unconnected-(JP2-Pad10)") (class "Default")
      (node (ref "JP2") (pin "10") (pinfunction "10_10") (pintype "passive"))
    )
    (net (code "57") (name "unconnected-(JP2-Pad11)") (class "Default")
      (node (ref "JP2") (pin "11") (pinfunction "11_11") (pintype "passive"))
    )
    (net (code "58") (name "unconnected-(JP2-Pad12)") (class "Default")
      (node (ref "JP2") (pin "12") (pinfunction "12_12") (pintype "passive"))
    )
    (net (code "59") (name "unconnected-(JP2-Pad14)") (class "Default")
      (node (ref "JP2") (pin "14") (pinfunction "14_14") (pintype "passive"))
    )
    (net (code "60") (name "unconnected-(JP2-Pad15)") (class "Default")
      (node (ref "JP2") (pin "15") (pinfunction "15_15") (pintype "passive"))
    )
    (net (code "61") (name "unconnected-(JP2-Pad16)") (class "Default")
      (node (ref "JP2") (pin "16") (pinfunction "16_16") (pintype "passive"))
    )
    (net (code "62") (name "unconnected-(JP2-Pad17)") (class "Default")
      (node (ref "JP2") (pin "17") (pinfunction "17_17") (pintype "passive"))
    )
    (net (code "63") (name "unconnected-(JP2-Pad19)") (class "Default")
      (node (ref "JP2") (pin "19") (pinfunction "19_19") (pintype "passive"))
    )
    (net (code "64") (name "unconnected-(JP3-Pad1)") (class "Default")
      (node (ref "JP3") (pin "1") (pinfunction "1_1") (pintype "passive"))
    )
    (net (code "65") (name "unconnected-(JP3-Pad3)") (class "Default")
      (node (ref "JP3") (pin "3") (pinfunction "3_3") (pintype "passive"))
    )
    (net (code "66") (name "unconnected-(JP3-Pad4)") (class "Default")
      (node (ref "JP3") (pin "4") (pinfunction "4_4") (pintype "passive"))
    )
    (net (code "67") (name "unconnected-(JP3-Pad5)") (class "Default")
      (node (ref "JP3") (pin "5") (pinfunction "5_5") (pintype "passive"))
    )
    (net (code "68") (name "unconnected-(JP3-Pad7)") (class "Default")
      (node (ref "JP3") (pin "7") (pinfunction "7_7") (pintype "passive"))
    )
    (net (code "69") (name "unconnected-(JP3-Pad8)") (class "Default")
      (node (ref "JP3") (pin "8") (pinfunction "8_8") (pintype "passive"))
    )
    (net (code "70") (name "unconnected-(JP3-Pad9)") (class "Default")
      (node (ref "JP3") (pin "9") (pinfunction "9_9") (pintype "passive"))
    )
    (net (code "71") (name "unconnected-(JP3-Pad10)") (class "Default")
      (node (ref "JP3") (pin "10") (pinfunction "10_10") (pintype "passive"))
    )
    (net (code "72") (name "unconnected-(JP3-Pad11)") (class "Default")
      (node (ref "JP3") (pin "11") (pinfunction "11_11") (pintype "passive"))
    )
    (net (code "73") (name "unconnected-(JP3-Pad13)") (class "Default")
      (node (ref "JP3") (pin "13") (pinfunction "13_13") (pintype "passive"))
    )
    (net (code "74") (name "unconnected-(JP3-Pad15)") (class "Default")
      (node (ref "JP3") (pin "15") (pinfunction "15_15") (pintype "passive"))
    )
    (net (code "75") (name "unconnected-(JP3-Pad16)") (class "Default")
      (node (ref "JP3") (pin "16") (pinfunction "16_16") (pintype "passive"))
    )
    (net (code "76") (name "unconnected-(JP3-Pad17)") (class "Default")
      (node (ref "JP3") (pin "17") (pinfunction "17_17") (pintype "passive"))
    )
    (net (code "77") (name "unconnected-(JP3-Pad18)") (class "Default")
      (node (ref "JP3") (pin "18") (pinfunction "18_18") (pintype "passive"))
    )
    (net (code "78") (name "unconnected-(JP3-Pad19)") (class "Default")
      (node (ref "JP3") (pin "19") (pinfunction "19_19") (pintype "passive"))
    )
    (net (code "79") (name "unconnected-(JP3-Pad20)") (class "Default")
      (node (ref "JP3") (pin "20") (pinfunction "20_20") (pintype "passive"))
    )
    (net (code "80") (name "unconnected-(JP7-Pad3)") (class "Default")
      (node (ref "JP7") (pin "3") (pinfunction "3_3") (pintype "passive"))
    )
    (net (code "81") (name "unconnected-(JP7-Pad4)") (class "Default")
      (node (ref "JP7") (pin "4") (pinfunction "4_4") (pintype "passive"))
    )
    (net (code "82") (name "unconnected-(JP7-Pad10)") (class "Default")
      (node (ref "JP7") (pin "10") (pinfunction "10_10") (pintype "passive"))
    )
    (net (code "83") (name "unconnected-(U2-Pad2)") (class "Default")
      (node (ref "U2") (pin "2") (pinfunction "2_2") (pintype "passive"))
    )
    (net (code "84") (name "unconnected-(U2-Pad5)") (class "Default")
      (node (ref "U2") (pin "5") (pinfunction "5_5") (pintype "passive"))
    )
    (net (code "85") (name "unconnected-(U2-Pad6)") (class "Default")
      (node (ref "U2") (pin "6") (pinfunction "6_6") (pintype "passive"))
    )
    (net (code "86") (name "unconnected-(U2-Pad7)") (class "Default")
      (node (ref "U2") (pin "7") (pinfunction "7_7") (pintype "passive"))
    )
    (net (code "87") (name "unconnected-(U2-Pad8)") (class "Default")
      (node (ref "U2") (pin "8") (pinfunction "8_8") (pintype "passive"))
    )
    (net (code "88") (name "unconnected-(U2-Pad9)") (class "Default")
      (node (ref "U2") (pin "9") (pinfunction "9_9") (pintype "passive"))
    )
    (net (code "89") (name "unconnected-(U3-Pad2)") (class "Default")
      (node (ref "U3") (pin "2") (pinfunction "2_2") (pintype "passive"))
    )
    (net (code "90") (name "unconnected-(U3-Pad5)") (class "Default")
      (node (ref "U3") (pin "5") (pinfunction "5_5") (pintype "passive"))
    )
    (net (code "91") (name "unconnected-(U3-Pad6)") (class "Default")
      (node (ref "U3") (pin "6") (pinfunction "6_6") (pintype "passive"))
    )
    (net (code "92") (name "unconnected-(U3-Pad7)") (class "Default")
      (node (ref "U3") (pin "7") (pinfunction "7_7") (pintype "passive"))
    )
    (net (code "93") (name "unconnected-(U3-Pad8)") (class "Default")
      (node (ref "U3") (pin "8") (pinfunction "8_8") (pintype "passive"))
    )
    (net (code "94") (name "unconnected-(U3-Pad9)") (class "Default")
      (node (ref "U3") (pin "9") (pinfunction "9_9") (pintype "passive"))
    )
    (net (code "95") (name "unconnected-(U4-Pad2)") (class "Default")
      (node (ref "U4") (pin "2") (pinfunction "2_2") (pintype "passive"))
    )
    (net (code "96") (name "unconnected-(U4-Pad5)") (class "Default")
      (node (ref "U4") (pin "5") (pinfunction "5_5") (pintype "passive"))
    )
    (net (code "97") (name "unconnected-(U4-Pad6)") (class "Default")
      (node (ref "U4") (pin "6") (pinfunction "6_6") (pintype "passive"))
    )
    (net (code "98") (name "unconnected-(U4-Pad7)") (class "Default")
      (node (ref "U4") (pin "7") (pinfunction "7_7") (pintype "passive"))
    )
    (net (code "99") (name "unconnected-(U4-Pad8)") (class "Default")
      (node (ref "U4") (pin "8") (pinfunction "8_8") (pintype "passive"))
    )
    (net (code "100") (name "unconnected-(U4-Pad9)") (class "Default")
      (node (ref "U4") (pin "9") (pinfunction "9_9") (pintype "passive"))
    )
  )
)
